# 13_-_UARTS.net
KiCad netlist of a schematic drawn in Altium Designer
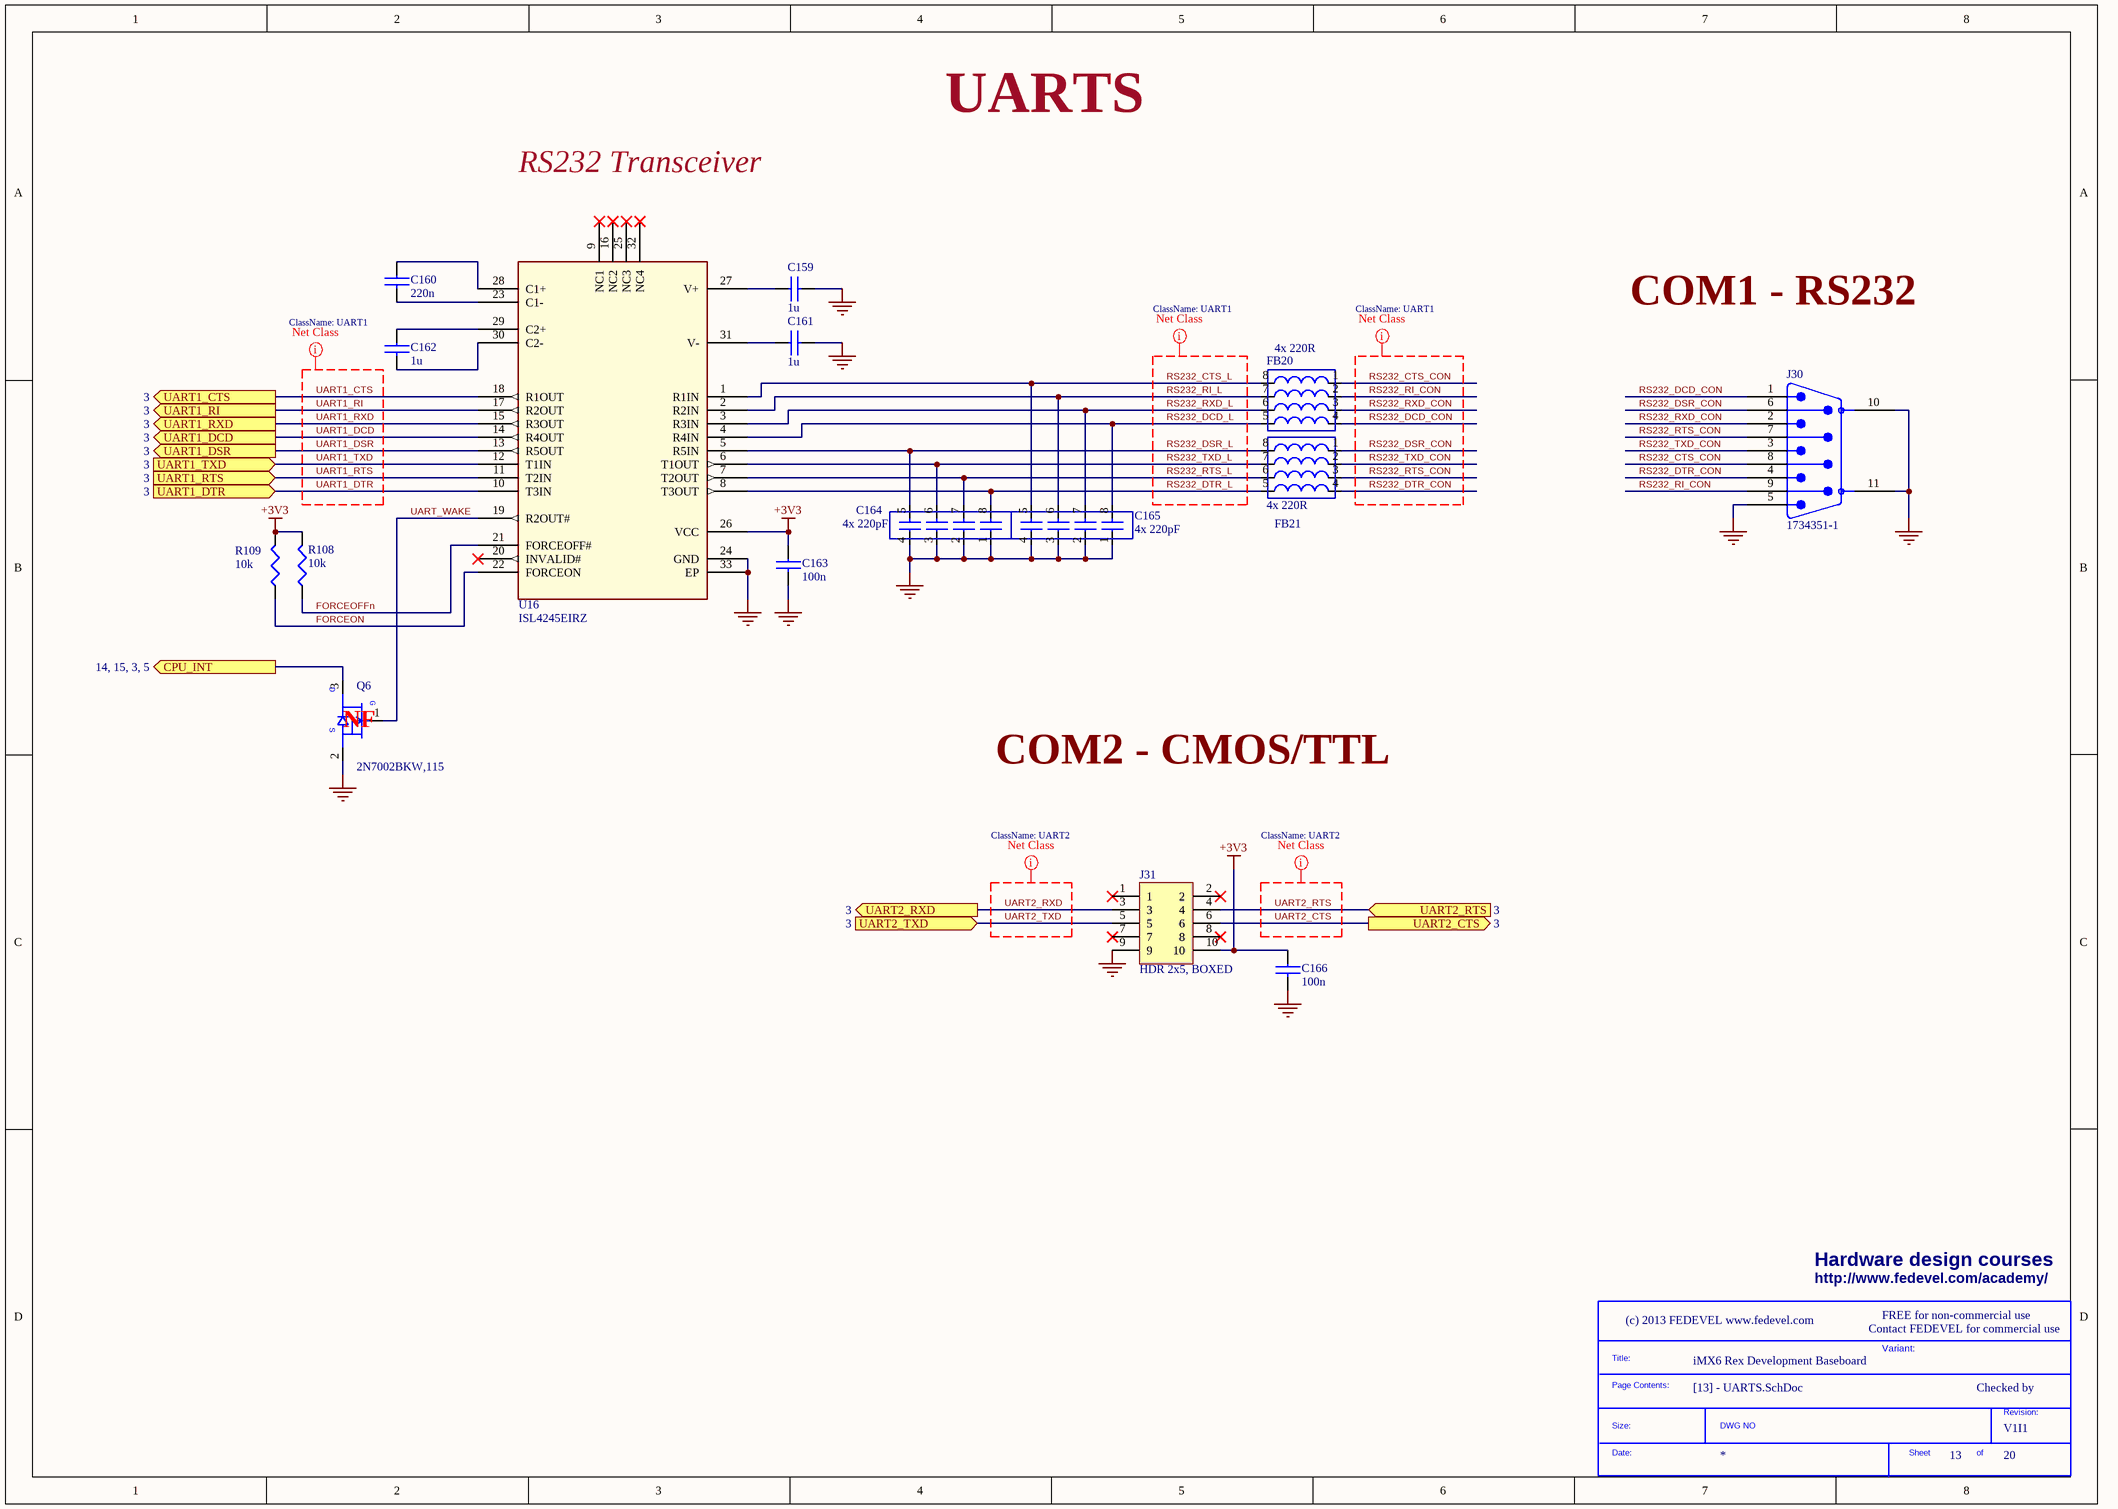
[diagram p0: [13] - UARTS.SchDoc]

(export (version "E")
  (design (tool "Eeschema 10.0.6"))
  (components
    (comp (ref "C159")
      (value "1u")
      (footprint "C0402")
      (description "CAP CER 1.0UF 16V X5R 0402")
      (fields
        (field (name "MANUFACTURER") "TDK Corporation")
        (field (name "MANUFACTURER PART NUMBER") "C1005X5R1C105K")
      )
      (libsource (lib "Integrated_Library_RF_FEB_2012") (part "C1005X5R1C105K"))
    )
    (comp (ref "C160")
      (value "220n")
      (footprint "C0402")
      (description "CAP CER .22UF 25V X5R 20% 0402")
      (fields
        (field (name "MANUFACTURER") "TDK Corporation")
        (field (name "MANUFACTURER PART NUMBER") "C1005X5R1E224M")
      )
      (libsource (lib "Integrated_Library_RF_FEB_2012") (part "C1005X5R1E224M"))
    )
    (comp (ref "C161")
      (value "1u")
      (footprint "C0402")
      (description "CAP CER 1.0UF 16V X5R 0402")
      (fields
        (field (name "MANUFACTURER") "TDK Corporation")
        (field (name "MANUFACTURER PART NUMBER") "C1005X5R1C105K")
      )
      (libsource (lib "Integrated_Library_RF_FEB_2012") (part "C1005X5R1C105K"))
    )
    (comp (ref "C162")
      (value "1u")
      (footprint "C0402")
      (description "CAP CER 1.0UF 16V X5R 0402")
      (fields
        (field (name "MANUFACTURER") "TDK Corporation")
        (field (name "MANUFACTURER PART NUMBER") "C1005X5R1C105K")
      )
      (libsource (lib "Integrated_Library_RF_FEB_2012") (part "C1005X5R1C105K"))
    )
    (comp (ref "C163")
      (value "100n")
      (footprint "C0402")
      (description "CAP CER .10UF 50V X5R 10% 0402")
      (fields
        (field (name "MANUFACTURER") "TDK Corporation")
        (field (name "MANUFACTURER PART NUMBER") "C1005X5R1H104K")
      )
      (libsource (lib "Integrated_Library_RF_FEB_2012") (part "C1005X5R1H104K"))
    )
    (comp (ref "C164")
      (value "4x 220pF")
      (footprint "4x_CAP_CC0805_CKCL44")
      (description "CAP ARRAY 4CH 220PF 50V 0805")
      (fields
        (field (name "MANUFACTURER") "TDK Corporation")
        (field (name "MANUFACTURER PART NUMBER") "CKCL44X7R1H221M")
        (field (name ".CHECKED PCB") "RF")
        (field (name ".CHECKED SCH") "RF")
      )
      (libsource (lib "Integrated_Library_RF_FEB_2012") (part "CKCL44X7R1H221M"))
    )
    (comp (ref "C165")
      (value "4x 220pF")
      (footprint "4x_CAP_CC0805_CKCL44")
      (description "CAP ARRAY 4CH 220PF 50V 0805")
      (fields
        (field (name "MANUFACTURER") "TDK Corporation")
        (field (name "MANUFACTURER PART NUMBER") "CKCL44X7R1H221M")
        (field (name ".CHECKED PCB") "RF")
        (field (name ".CHECKED SCH") "RF")
      )
      (libsource (lib "Integrated_Library_RF_FEB_2012") (part "CKCL44X7R1H221M"))
    )
    (comp (ref "C166")
      (value "100n")
      (footprint "C0402")
      (description "CAP CER .10UF 50V X5R 10% 0402")
      (fields
        (field (name "MANUFACTURER") "TDK Corporation")
        (field (name "MANUFACTURER PART NUMBER") "C1005X5R1H104K")
      )
      (libsource (lib "Integrated_Library_RF_FEB_2012") (part "C1005X5R1H104K"))
    )
    (comp (ref "FB20")
      (value "4x 220R")
      (footprint "4x0402_BLA2A_MURATA")
      (description "FERRITE ARRAY 220 OHM 0804 SMD")
      (fields
        (field (name "MANUFACTURER") "Murata Electronics North America")
        (field (name "MANUFACTURER PART NUMBER") "BLA2ABB221SN4D")
        (field (name ".CHECKED PCB") "RF")
        (field (name ".CHECKED SCH") "RF")
      )
      (libsource (lib "Integrated_Library_RF_FEB_2012") (part "BLA2ABB221SN4D"))
    )
    (comp (ref "FB21")
      (value "4x 220R")
      (footprint "4x0402_BLA2A_MURATA")
      (description "FERRITE ARRAY 220 OHM 0804 SMD")
      (fields
        (field (name "MANUFACTURER") "Murata Electronics North America")
        (field (name "MANUFACTURER PART NUMBER") "BLA2ABB221SN4D")
        (field (name ".CHECKED PCB") "RF")
        (field (name ".CHECKED SCH") "RF")
      )
      (libsource (lib "Integrated_Library_RF_FEB_2012") (part "BLA2ABB221SN4D"))
    )
    (comp (ref "J30")
      (value "1734351-1")
      (footprint "DBA9_M_RA")
      (description "CONN D-SUB PLUG R/A 9POS GOLD/FL")
      (fields (field (name "MANUFACTURER") "TE Connectivity"))
      (libsource (lib "Integrated_Library_RF_FEB_2012") (part "1734351-1"))
    )
    (comp (ref "J31")
      (value "HDR 2x5, BOXED")
      (footprint "HDR_2x5_2.54mm_BOXED")
      (description "CONN HEADER 10POS VERT 10GOLD")
      (fields
        (field (name "MANUFACTURER") "3M")
        (field (name "MANUFACTURER PART NUMBER") "D2510-6002-AR")
        (field (name ".CREATOR") "MM")
        (field (name ".CHECKED PCB") "MM")
        (field (name ".CHECKED SCH") "MM")
      )
      (libsource (lib "Integrated_Library_RF_FEB_2012") (part "D2510-6002-AR"))
    )
    (comp (ref "Q6")
      (value "2N7002BKW,115")
      (footprint "SC70_SOT323")
      (description "MOSFET N-CH 60V 310MA SOT323")
      (fields
        (field (name "MANUFACTURER") "NXP Semiconductors")
        (field (name ".CHECKED PCB") "RF")
        (field (name ".CHECKED SCH") "RF")
      )
      (libsource (lib "Integrated_Library_RF_FEB_2012") (part "2N7002BKW,115"))
    )
    (comp (ref "R108")
      (value "10k")
      (footprint "R0402")
      (description "RES 10.0K OHM 1/16W 1% 0402 SMD")
      (fields
        (field (name "MANUFACTURER") "Yageo")
        (field (name "MANUFACTURER PART NUMBER") "RC0402FR-0710KL")
      )
      (libsource (lib "Integrated_Library_RF_FEB_2012") (part "RC0402FR-0710KL"))
    )
    (comp (ref "R109")
      (value "10k")
      (footprint "R0402")
      (description "RES 10.0K OHM 1/16W 1% 0402 SMD")
      (fields
        (field (name "MANUFACTURER") "Yageo")
        (field (name "MANUFACTURER PART NUMBER") "RC0402FR-0710KL")
      )
      (libsource (lib "Integrated_Library_RF_FEB_2012") (part "RC0402FR-0710KL"))
    )
    (comp (ref "U16")
      (value "ISL4245EIRZ")
      (footprint "QFN32 5x5x0.85")
      (description "IC 3DRVR/5RCVR RS232 3V 32-QFN")
      (fields
        (field (name "MANUFACTURER") "Intersil")
        (field (name ".CHECKED PCB") "RF")
        (field (name ".CHECKED SCH") "RF")
      )
      (libsource (lib "Integrated_Library_RF_FEB_2012") (part "ISL4245EIRZ"))
    )
  )
  (nets
    (net (code "1") (name "+3V3") (class "Default")
      (node (ref "C163") (pin "1") (pinfunction "1_1") (pintype "passive"))
      (node (ref "C166") (pin "1") (pinfunction "1_1") (pintype "passive"))
      (node (ref "J31") (pin "10") (pinfunction "10_10") (pintype "passive"))
      (node (ref "R108") (pin "2") (pinfunction "2_2") (pintype "passive"))
      (node (ref "R109") (pin "2") (pinfunction "2_2") (pintype "passive"))
      (node (ref "U16") (pin "26") (pinfunction "VCC_26") (pintype "power_in"))
    )
    (net (code "2") (name "/CPU_INT") (class "Default")
      (node (ref "Q6") (pin "3") (pinfunction "DRAIN_3") (pintype "passive"))
    )
    (net (code "3") (name "/FORCEOFFn") (class "Default")
      (node (ref "R108") (pin "1") (pinfunction "1_1") (pintype "passive"))
      (node (ref "U16") (pin "21") (pinfunction "FORCEOFF#_21") (pintype "passive"))
    )
    (net (code "4") (name "/FORCEON") (class "Default")
      (node (ref "R109") (pin "1") (pinfunction "1_1") (pintype "passive"))
      (node (ref "U16") (pin "22") (pinfunction "FORCEON_22") (pintype "passive"))
    )
    (net (code "5") (name "/RS232_CTS_CON") (class "Default")
      (node (ref "FB20") (pin "1") (pinfunction "1_1") (pintype "passive"))
      (node (ref "J30") (pin "8") (pinfunction "16_8") (pintype "passive"))
    )
    (net (code "6") (name "/RS232_CTS_L") (class "Default")
      (node (ref "C165") (pin "5") (pinfunction "5_5") (pintype "passive"))
      (node (ref "FB20") (pin "8") (pinfunction "8_8") (pintype "passive"))
      (node (ref "U16") (pin "1") (pinfunction "R1IN_1") (pintype "passive"))
    )
    (net (code "7") (name "/RS232_DCD_CON") (class "Default")
      (node (ref "FB20") (pin "4") (pinfunction "4_4") (pintype "passive"))
      (node (ref "J30") (pin "1") (pinfunction "1_1") (pintype "passive"))
    )
    (net (code "8") (name "/RS232_DCD_L") (class "Default")
      (node (ref "C165") (pin "8") (pinfunction "8_8") (pintype "passive"))
      (node (ref "FB20") (pin "5") (pinfunction "5_5") (pintype "passive"))
      (node (ref "U16") (pin "4") (pinfunction "R4IN_4") (pintype "passive"))
    )
    (net (code "9") (name "/RS232_DSR_CON") (class "Default")
      (node (ref "FB21") (pin "1") (pinfunction "1_1") (pintype "passive"))
      (node (ref "J30") (pin "6") (pinfunction "14_6") (pintype "passive"))
    )
    (net (code "10") (name "/RS232_DSR_L") (class "Default")
      (node (ref "C164") (pin "5") (pinfunction "5_5") (pintype "passive"))
      (node (ref "FB21") (pin "8") (pinfunction "8_8") (pintype "passive"))
      (node (ref "U16") (pin "5") (pinfunction "R5IN_5") (pintype "passive"))
    )
    (net (code "11") (name "/RS232_DTR_CON") (class "Default")
      (node (ref "FB21") (pin "4") (pinfunction "4_4") (pintype "passive"))
      (node (ref "J30") (pin "4") (pinfunction "4_4") (pintype "passive"))
    )
    (net (code "12") (name "/RS232_DTR_L") (class "Default")
      (node (ref "C164") (pin "8") (pinfunction "8_8") (pintype "passive"))
      (node (ref "FB21") (pin "5") (pinfunction "5_5") (pintype "passive"))
      (node (ref "U16") (pin "8") (pinfunction "T3OUT_8") (pintype "output"))
    )
    (net (code "13") (name "/RS232_RI_CON") (class "Default")
      (node (ref "FB20") (pin "2") (pinfunction "2_2") (pintype "passive"))
      (node (ref "J30") (pin "9") (pinfunction "17_9") (pintype "passive"))
    )
    (net (code "14") (name "/RS232_RI_L") (class "Default")
      (node (ref "C165") (pin "6") (pinfunction "6_6") (pintype "passive"))
      (node (ref "FB20") (pin "7") (pinfunction "7_7") (pintype "passive"))
      (node (ref "U16") (pin "2") (pinfunction "R2IN_2") (pintype "passive"))
    )
    (net (code "15") (name "/RS232_RTS_CON") (class "Default")
      (node (ref "FB21") (pin "3") (pinfunction "3_3") (pintype "passive"))
      (node (ref "J30") (pin "7") (pinfunction "15_7") (pintype "passive"))
    )
    (net (code "16") (name "/RS232_RTS_L") (class "Default")
      (node (ref "C164") (pin "7") (pinfunction "7_7") (pintype "passive"))
      (node (ref "FB21") (pin "6") (pinfunction "6_6") (pintype "passive"))
      (node (ref "U16") (pin "7") (pinfunction "T2OUT_7") (pintype "output"))
    )
    (net (code "17") (name "/RS232_RXD_CON") (class "Default")
      (node (ref "FB20") (pin "3") (pinfunction "3_3") (pintype "passive"))
      (node (ref "J30") (pin "2") (pinfunction "2_2") (pintype "passive"))
    )
    (net (code "18") (name "/RS232_RXD_L") (class "Default")
      (node (ref "C165") (pin "7") (pinfunction "7_7") (pintype "passive"))
      (node (ref "FB20") (pin "6") (pinfunction "6_6") (pintype "passive"))
      (node (ref "U16") (pin "3") (pinfunction "R3IN_3") (pintype "passive"))
    )
    (net (code "19") (name "/RS232_TXD_CON") (class "Default")
      (node (ref "FB21") (pin "2") (pinfunction "2_2") (pintype "passive"))
      (node (ref "J30") (pin "3") (pinfunction "3_3") (pintype "passive"))
    )
    (net (code "20") (name "/RS232_TXD_L") (class "Default")
      (node (ref "C164") (pin "6") (pinfunction "6_6") (pintype "passive"))
      (node (ref "FB21") (pin "7") (pinfunction "7_7") (pintype "passive"))
      (node (ref "U16") (pin "6") (pinfunction "T1OUT_6") (pintype "output"))
    )
    (net (code "21") (name "/UART1_CTS") (class "Default")
      (node (ref "U16") (pin "18") (pinfunction "R1OUT_18") (pintype "output"))
    )
    (net (code "22") (name "/UART1_DCD") (class "Default")
      (node (ref "U16") (pin "14") (pinfunction "R4OUT_14") (pintype "output"))
    )
    (net (code "23") (name "/UART1_DSR") (class "Default")
      (node (ref "U16") (pin "13") (pinfunction "R5OUT_13") (pintype "output"))
    )
    (net (code "24") (name "/UART1_DTR") (class "Default")
      (node (ref "U16") (pin "10") (pinfunction "T3IN_10") (pintype "passive"))
    )
    (net (code "25") (name "/UART1_RI") (class "Default")
      (node (ref "U16") (pin "17") (pinfunction "R2OUT_17") (pintype "output"))
    )
    (net (code "26") (name "/UART1_RTS") (class "Default")
      (node (ref "U16") (pin "11") (pinfunction "T2IN_11") (pintype "passive"))
    )
    (net (code "27") (name "/UART1_RXD") (class "Default")
      (node (ref "U16") (pin "15") (pinfunction "R3OUT_15") (pintype "output"))
    )
    (net (code "28") (name "/UART1_TXD") (class "Default")
      (node (ref "U16") (pin "12") (pinfunction "T1IN_12") (pintype "passive"))
    )
    (net (code "29") (name "/UART2_CTS") (class "Default")
      (node (ref "J31") (pin "6") (pinfunction "6_6") (pintype "passive"))
    )
    (net (code "30") (name "/UART2_RTS") (class "Default")
      (node (ref "J31") (pin "4") (pinfunction "4_4") (pintype "passive"))
    )
    (net (code "31") (name "/UART2_RXD") (class "Default")
      (node (ref "J31") (pin "3") (pinfunction "3_3") (pintype "passive"))
    )
    (net (code "32") (name "/UART2_TXD") (class "Default")
      (node (ref "J31") (pin "5") (pinfunction "5_5") (pintype "passive"))
    )
    (net (code "33") (name "/UART_WAKE") (class "Default")
      (node (ref "Q6") (pin "1") (pinfunction "GATE_1") (pintype "passive"))
      (node (ref "U16") (pin "19") (pinfunction "R2OUT#_19") (pintype "output"))
    )
    (net (code "34") (name "GND") (class "Default")
      (node (ref "C159") (pin "2") (pinfunction "2_2") (pintype "passive"))
      (node (ref "C161") (pin "2") (pinfunction "2_2") (pintype "passive"))
      (node (ref "C163") (pin "2") (pinfunction "2_2") (pintype "passive"))
      (node (ref "C164") (pin "1") (pinfunction "1_1") (pintype "passive"))
      (node (ref "C164") (pin "2") (pinfunction "2_2") (pintype "passive"))
      (node (ref "C164") (pin "3") (pinfunction "3_3") (pintype "passive"))
      (node (ref "C164") (pin "4") (pinfunction "4_4") (pintype "passive"))
      (node (ref "C165") (pin "1") (pinfunction "1_1") (pintype "passive"))
      (node (ref "C165") (pin "2") (pinfunction "2_2") (pintype "passive"))
      (node (ref "C165") (pin "3") (pinfunction "3_3") (pintype "passive"))
      (node (ref "C165") (pin "4") (pinfunction "4_4") (pintype "passive"))
      (node (ref "C166") (pin "2") (pinfunction "2_2") (pintype "passive"))
      (node (ref "J30") (pin "10") (pinfunction "SHIELD_10") (pintype "passive"))
      (node (ref "J30") (pin "11") (pinfunction "SHIELD_11") (pintype "passive"))
      (node (ref "J30") (pin "5") (pinfunction "5_5") (pintype "passive"))
      (node (ref "J31") (pin "9") (pinfunction "9_9") (pintype "passive"))
      (node (ref "Q6") (pin "2") (pinfunction "SOURCE_2") (pintype "passive"))
      (node (ref "U16") (pin "24") (pinfunction "GND_24") (pintype "power_in"))
      (node (ref "U16") (pin "33") (pinfunction "EP_33") (pintype "power_in"))
    )
    (net (code "35") (name "Net-(U16-C1+)") (class "Default")
      (node (ref "C160") (pin "1") (pinfunction "1_1") (pintype "passive"))
      (node (ref "U16") (pin "28") (pinfunction "C1+_28") (pintype "passive"))
    )
    (net (code "36") (name "Net-(U16-C1-)") (class "Default")
      (node (ref "C160") (pin "2") (pinfunction "2_2") (pintype "passive"))
      (node (ref "U16") (pin "23") (pinfunction "C1-_23") (pintype "passive"))
    )
    (net (code "37") (name "Net-(U16-C2+)") (class "Default")
      (node (ref "C162") (pin "1") (pinfunction "1_1") (pintype "passive"))
      (node (ref "U16") (pin "29") (pinfunction "C2+_29") (pintype "passive"))
    )
    (net (code "38") (name "Net-(U16-C2-)") (class "Default")
      (node (ref "C162") (pin "2") (pinfunction "2_2") (pintype "passive"))
      (node (ref "U16") (pin "30") (pinfunction "C2-_30") (pintype "passive"))
    )
    (net (code "39") (name "Net-(U16-V+)") (class "Default")
      (node (ref "C159") (pin "1") (pinfunction "1_1") (pintype "passive"))
      (node (ref "U16") (pin "27") (pinfunction "V+_27") (pintype "passive"))
    )
    (net (code "40") (name "Net-(U16-V-)") (class "Default")
      (node (ref "C161") (pin "1") (pinfunction "1_1") (pintype "passive"))
      (node (ref "U16") (pin "31") (pinfunction "V-_31") (pintype "passive"))
    )
    (net (code "41") (name "unconnected-(J31-Pad1)") (class "Default")
      (node (ref "J31") (pin "1") (pinfunction "1_1") (pintype "passive+no_connect"))
    )
    (net (code "42") (name "unconnected-(J31-Pad2)") (class "Default")
      (node (ref "J31") (pin "2") (pinfunction "2_2") (pintype "passive+no_connect"))
    )
    (net (code "43") (name "unconnected-(J31-Pad7)") (class "Default")
      (node (ref "J31") (pin "7") (pinfunction "7_7") (pintype "passive+no_connect"))
    )
    (net (code "44") (name "unconnected-(J31-Pad8)") (class "Default")
      (node (ref "J31") (pin "8") (pinfunction "8_8") (pintype "passive+no_connect"))
    )
    (net (code "45") (name "unconnected-(U16-INVALID#-Pad20)") (class "Default")
      (node (ref "U16") (pin "20") (pinfunction "INVALID#_20") (pintype "output+no_connect"))
    )
    (net (code "46") (name "unconnected-(U16-NC1-Pad9)") (class "Default")
      (node (ref "U16") (pin "9") (pinfunction "NC1_9") (pintype "passive+no_connect"))
    )
    (net (code "47") (name "unconnected-(U16-NC2-Pad16)") (class "Default")
      (node (ref "U16") (pin "16") (pinfunction "NC2_16") (pintype "passive+no_connect"))
    )
    (net (code "48") (name "unconnected-(U16-NC3-Pad25)") (class "Default")
      (node (ref "U16") (pin "25") (pinfunction "NC3_25") (pintype "passive+no_connect"))
    )
    (net (code "49") (name "unconnected-(U16-NC4-Pad32)") (class "Default")
      (node (ref "U16") (pin "32") (pinfunction "NC4_32") (pintype "passive+no_connect"))
    )
  )
)
